# EMP1.net
KiCad netlist of a schematic drawn in EAGLE
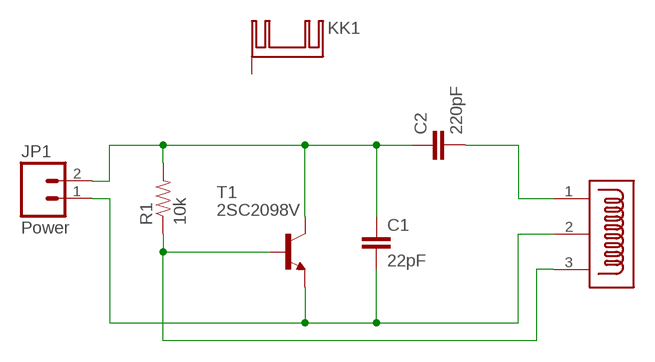
[diagram p0: schematic, sheet 1]

(export (version "E")
  (design (tool "Eeschema 10.0.6"))
  (components
    (comp (ref "C1")
      (value "22pF")
      (footprint "eagle-import:CAP-PTH-SMALL")
      (libsource (lib "eagle-import") (part "CAPPTH"))
    )
    (comp (ref "C2")
      (value "220pF")
      (footprint "eagle-import:CAP-PTH-SMALL")
      (libsource (lib "eagle-import") (part "CAPPTH"))
    )
    (comp (ref "JP1")
      (value "Power")
      (footprint "eagle-import:1X02")
      (libsource (lib "eagle-import") (part "M02PTH"))
    )
    (comp (ref "KK1")
      (value "D03PA-PAD")
      (footprint "eagle-import:D03PA-PAD")
      (libsource (lib "eagle-import") (part "D03PA-PAD"))
    )
    (comp (ref "R1")
      (value "10k")
      (footprint "eagle-import:AXIAL-0.4")
      (libsource (lib "eagle-import") (part "RESISTORPTH-1/4W"))
    )
    (comp (ref "T1")
      (value "2SC2098V")
      (footprint "eagle-import:TO220AV")
      (libsource (lib "eagle-import") (part "2SC2098V"))
    )
    (comp (ref "U$1")
      (value "EMP_WIRE")
      (footprint "eagle-import:EMP_WIRE")
      (libsource (lib "eagle-import") (part "EMP_WIRE"))
    )
  )
  (nets
    (net (code "1") (name "Net-(C2-Pad2)") (class "Default")
      (node (ref "C2") (pin "2") (pinfunction "2_2") (pintype "passive"))
      (node (ref "U$1") (pin "1") (pinfunction "1_1") (pintype "bidirectional"))
    )
    (net (code "2") (name "Net-(R1-1)") (class "Default")
      (node (ref "R1") (pin "P$1") (pinfunction "1_P$1") (pintype "passive"))
      (node (ref "T1") (pin "1") (pinfunction "B_1") (pintype "passive"))
      (node (ref "U$1") (pin "3") (pinfunction "3_3") (pintype "bidirectional"))
    )
    (net (code "3") (name "Net-(R1-2)") (class "Default")
      (node (ref "C1") (pin "1") (pinfunction "1_1") (pintype "passive"))
      (node (ref "C2") (pin "1") (pinfunction "1_1") (pintype "passive"))
      (node (ref "JP1") (pin "2") (pinfunction "2_2") (pintype "passive"))
      (node (ref "R1") (pin "P$2") (pinfunction "2_P$2") (pintype "passive"))
      (node (ref "T1") (pin "2") (pinfunction "C_2") (pintype "passive"))
    )
    (net (code "4") (name "Net-(T1-E)") (class "Default")
      (node (ref "C1") (pin "2") (pinfunction "2_2") (pintype "passive"))
      (node (ref "JP1") (pin "1") (pinfunction "1_1") (pintype "passive"))
      (node (ref "T1") (pin "3") (pinfunction "E_3") (pintype "passive"))
      (node (ref "U$1") (pin "2") (pinfunction "2_2") (pintype "bidirectional"))
    )
    (net (code "5") (name "unconnected-(KK1-K-PadB)") (class "Default")
      (node (ref "KK1") (pin "B") (pinfunction "K_B") (pintype "passive"))
    )
  )
)
